# sabotter.net
KiCad netlist of a schematic drawn in EAGLE
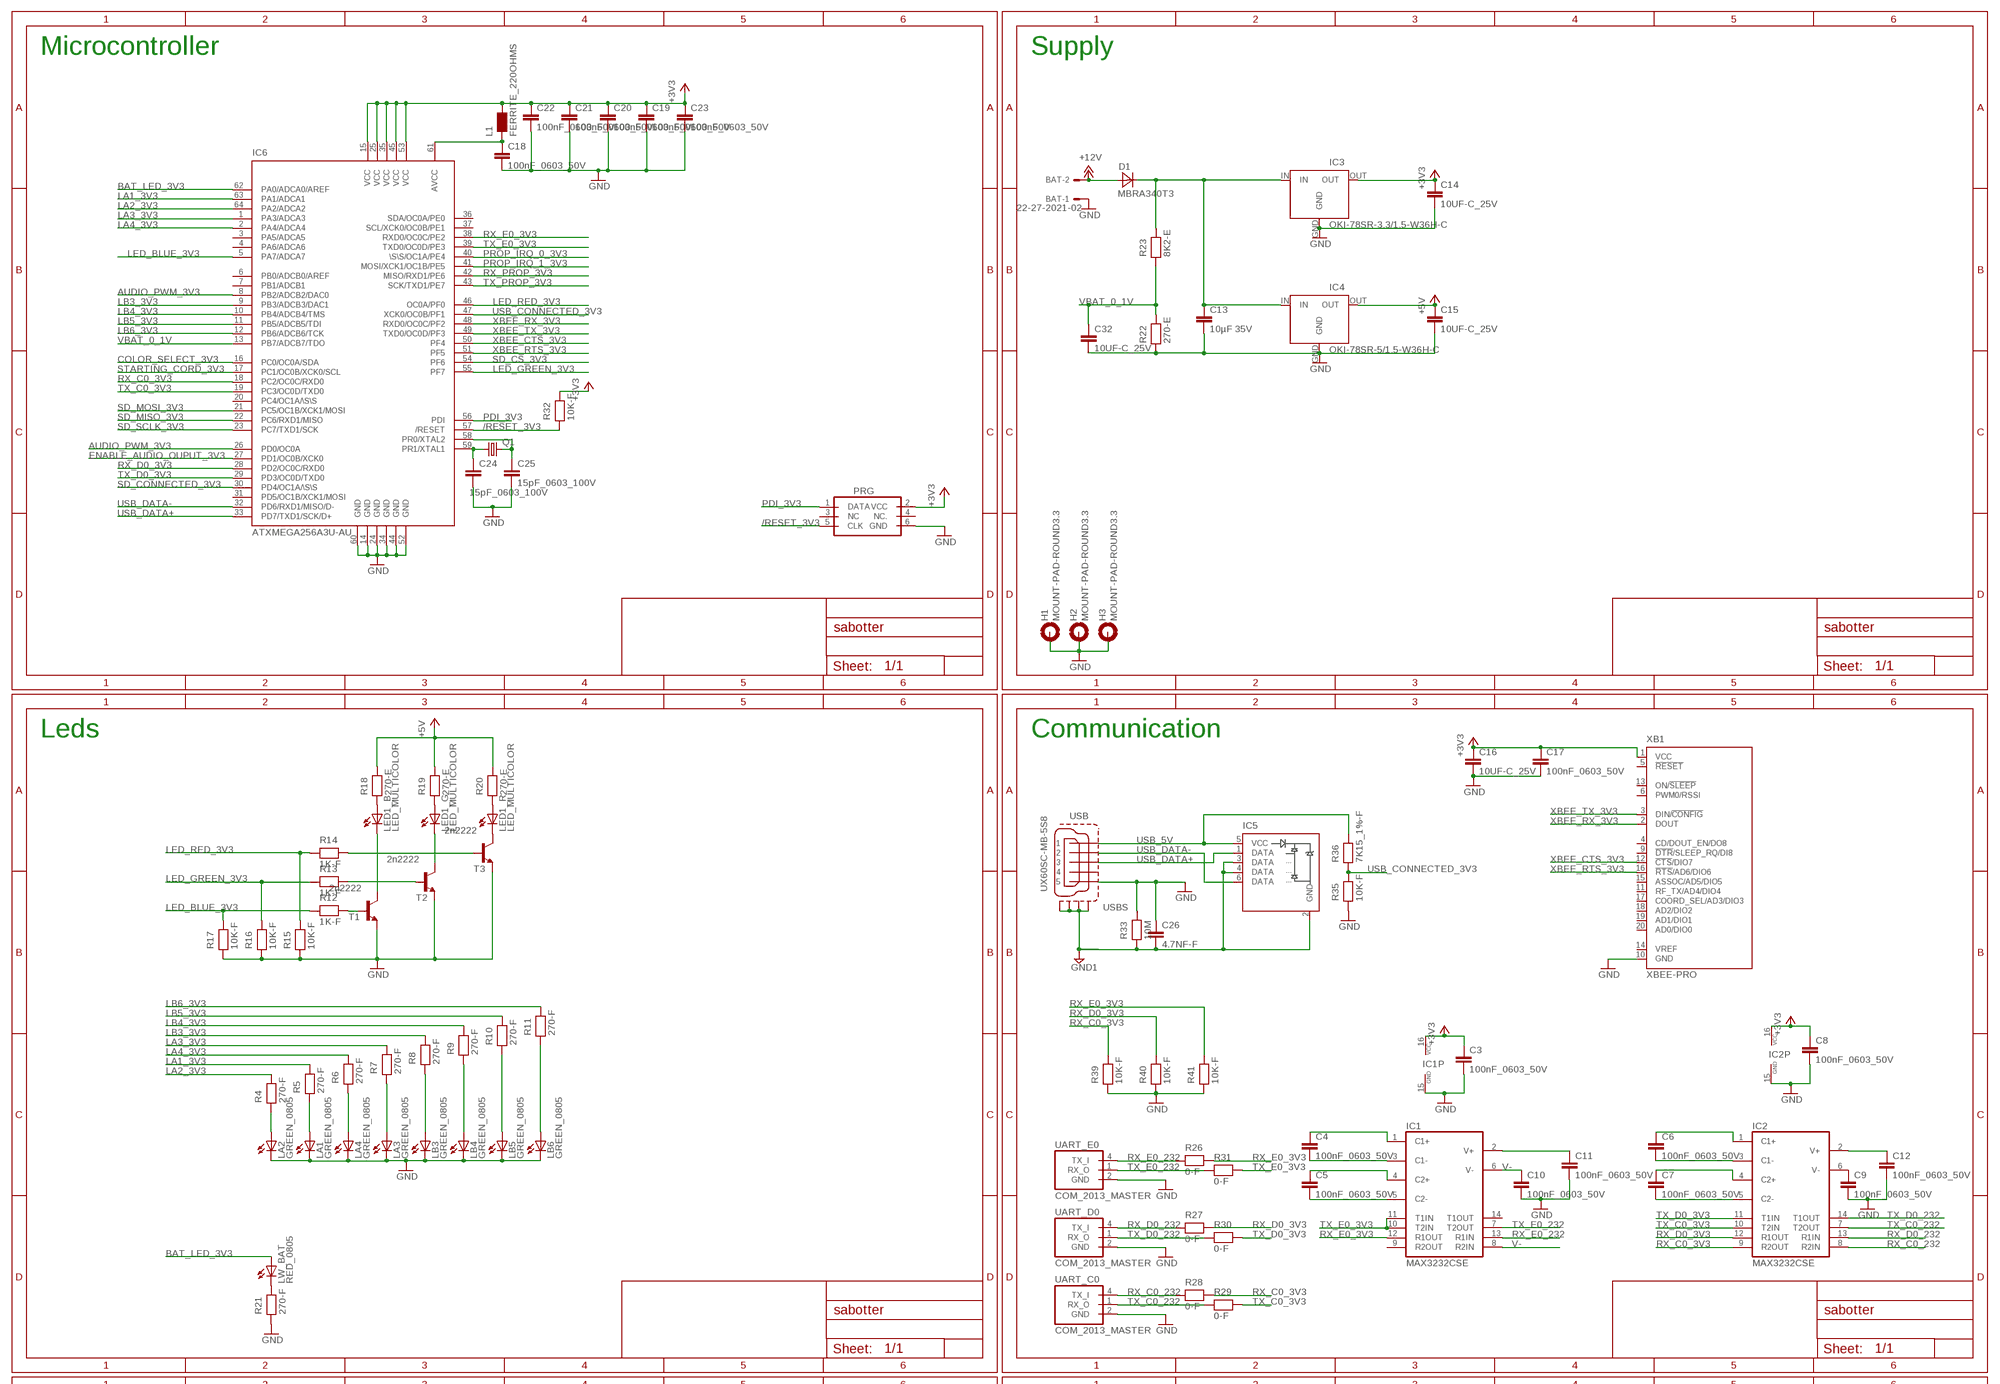
[diagram p0: schematic, sheet 1, part 1 of 2]
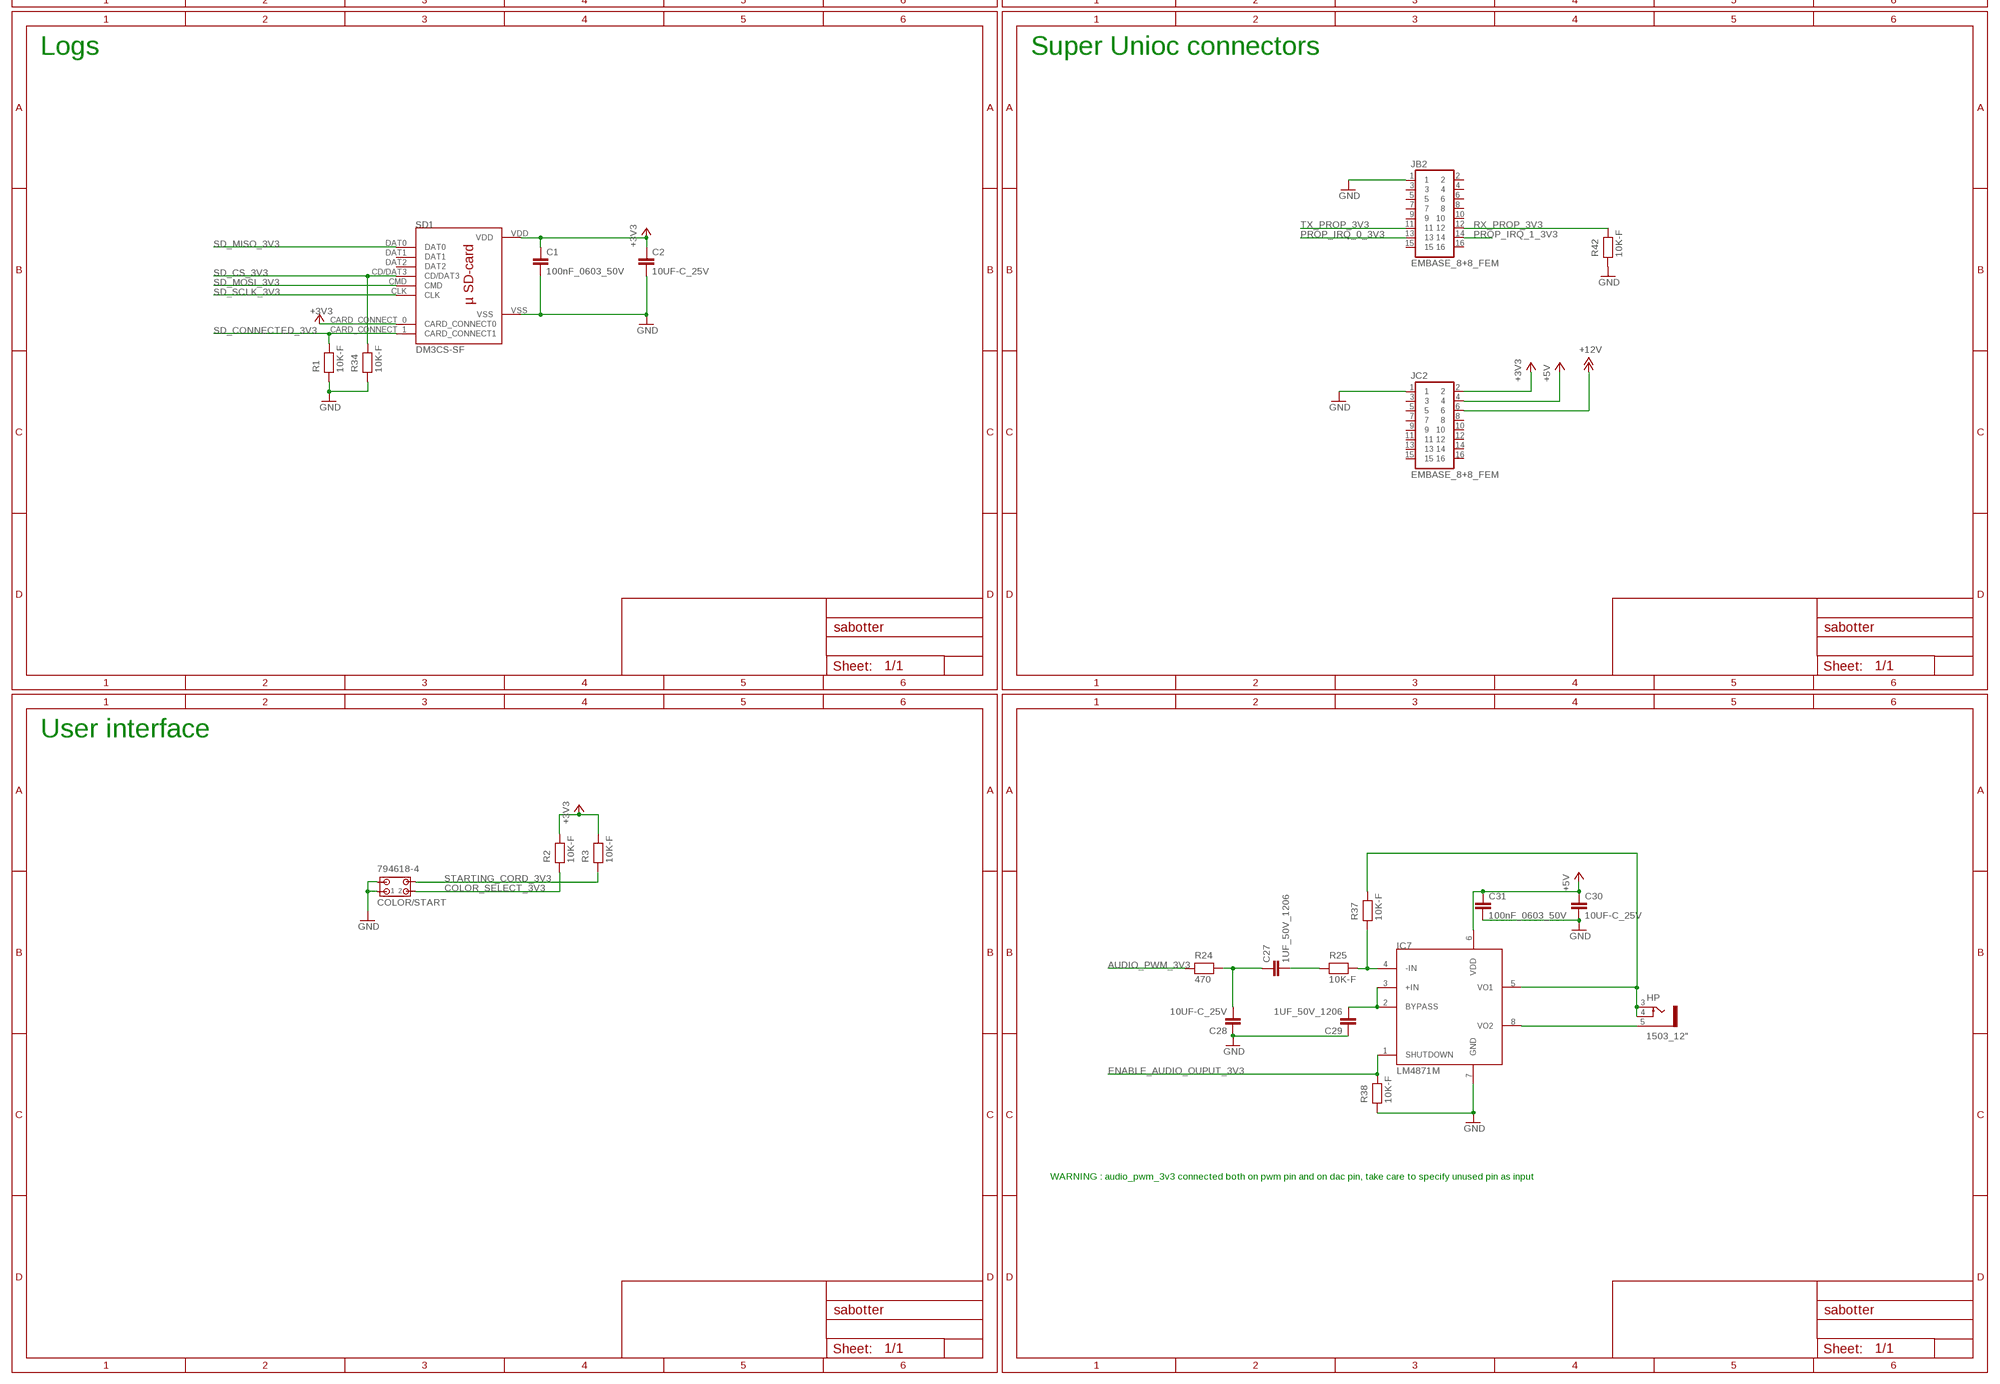
[diagram p1: schematic, sheet 1, part 2 of 2]

(export (version "E")
  (design (tool "Eeschema 10.0.6"))
  (components
    (comp (ref "BAT")
      (value "22-27-2021-02")
      (footprint "eagle-import:6410-02")
      (libsource (lib "eagle-import") (part "22-?-0227-2021"))
    )
    (comp (ref "C1")
      (value "100nF_0603_50V")
      (footprint "eagle-import:C0603")
      (libsource (lib "eagle-import") (part "100NF-F"))
    )
    (comp (ref "C2")
      (value "10UF-C_25V")
      (footprint "eagle-import:C1210")
      (libsource (lib "eagle-import") (part "10UF-C_25V"))
    )
    (comp (ref "C3")
      (value "100nF_0603_50V")
      (footprint "eagle-import:C0603")
      (libsource (lib "eagle-import") (part "100NF-F"))
    )
    (comp (ref "C4")
      (value "100nF_0603_50V")
      (footprint "eagle-import:C0603")
      (libsource (lib "eagle-import") (part "100NF-F"))
    )
    (comp (ref "C5")
      (value "100nF_0603_50V")
      (footprint "eagle-import:C0603")
      (libsource (lib "eagle-import") (part "100NF-F"))
    )
    (comp (ref "C6")
      (value "100nF_0603_50V")
      (footprint "eagle-import:C0603")
      (libsource (lib "eagle-import") (part "100NF-F"))
    )
    (comp (ref "C7")
      (value "100nF_0603_50V")
      (footprint "eagle-import:C0603")
      (libsource (lib "eagle-import") (part "100NF-F"))
    )
    (comp (ref "C8")
      (value "100nF_0603_50V")
      (footprint "eagle-import:C0603")
      (libsource (lib "eagle-import") (part "100NF-F"))
    )
    (comp (ref "C9")
      (value "100nF_0603_50V")
      (footprint "eagle-import:C0603")
      (libsource (lib "eagle-import") (part "100NF-F"))
    )
    (comp (ref "C10")
      (value "100nF_0603_50V")
      (footprint "eagle-import:C0603")
      (libsource (lib "eagle-import") (part "100NF-F"))
    )
    (comp (ref "C11")
      (value "100nF_0603_50V")
      (footprint "eagle-import:C0603")
      (libsource (lib "eagle-import") (part "100NF-F"))
    )
    (comp (ref "C12")
      (value "100nF_0603_50V")
      (footprint "eagle-import:C0603")
      (libsource (lib "eagle-import") (part "100NF-F"))
    )
    (comp (ref "C13")
      (value "10µF 35V")
      (footprint "eagle-import:C1210")
      (libsource (lib "eagle-import") (part "10UF-C_35V"))
    )
    (comp (ref "C14")
      (value "10UF-C_25V")
      (footprint "eagle-import:C1210")
      (libsource (lib "eagle-import") (part "10UF-C_25V"))
    )
    (comp (ref "C15")
      (value "10UF-C_25V")
      (footprint "eagle-import:C1210")
      (libsource (lib "eagle-import") (part "10UF-C_25V"))
    )
    (comp (ref "C16")
      (value "10UF-C_25V")
      (footprint "eagle-import:C1210")
      (libsource (lib "eagle-import") (part "10UF-C_25V"))
    )
    (comp (ref "C17")
      (value "100nF_0603_50V")
      (footprint "eagle-import:C0603")
      (libsource (lib "eagle-import") (part "100NF-F"))
    )
    (comp (ref "C18")
      (value "100nF_0603_50V")
      (footprint "eagle-import:C0603")
      (libsource (lib "eagle-import") (part "100NF-F"))
    )
    (comp (ref "C19")
      (value "100nF_0603_50V")
      (footprint "eagle-import:C0603")
      (libsource (lib "eagle-import") (part "100NF-F"))
    )
    (comp (ref "C20")
      (value "100nF_0603_50V")
      (footprint "eagle-import:C0603")
      (libsource (lib "eagle-import") (part "100NF-F"))
    )
    (comp (ref "C21")
      (value "100nF_0603_50V")
      (footprint "eagle-import:C0603")
      (libsource (lib "eagle-import") (part "100NF-F"))
    )
    (comp (ref "C22")
      (value "100nF_0603_50V")
      (footprint "eagle-import:C0603")
      (libsource (lib "eagle-import") (part "100NF-F"))
    )
    (comp (ref "C23")
      (value "100nF_0603_50V")
      (footprint "eagle-import:C0603")
      (libsource (lib "eagle-import") (part "100NF-F"))
    )
    (comp (ref "C24")
      (value "15pF_0603_100V")
      (footprint "eagle-import:C0603")
      (libsource (lib "eagle-import") (part "15PF-F"))
    )
    (comp (ref "C25")
      (value "15pF_0603_100V")
      (footprint "eagle-import:C0603")
      (libsource (lib "eagle-import") (part "15PF-F"))
    )
    (comp (ref "C26")
      (value "4.7NF-F")
      (footprint "eagle-import:C0603")
      (libsource (lib "eagle-import") (part "4.7NF-F"))
    )
    (comp (ref "C27")
      (value "1UF_50V_1206")
      (footprint "eagle-import:C1206")
      (libsource (lib "eagle-import") (part "1UFD_25V"))
    )
    (comp (ref "C28")
      (value "10UF-C_25V")
      (footprint "eagle-import:C1210")
      (libsource (lib "eagle-import") (part "10UF-C_25V"))
    )
    (comp (ref "C29")
      (value "1UF_50V_1206")
      (footprint "eagle-import:C1206")
      (libsource (lib "eagle-import") (part "1UFD_25V"))
    )
    (comp (ref "C30")
      (value "10UF-C_25V")
      (footprint "eagle-import:C1210")
      (libsource (lib "eagle-import") (part "10UF-C_25V"))
    )
    (comp (ref "C31")
      (value "100nF_0603_50V")
      (footprint "eagle-import:C0603")
      (libsource (lib "eagle-import") (part "100NF-F"))
    )
    (comp (ref "C32")
      (value "10UF-C_25V")
      (footprint "eagle-import:C1210")
      (libsource (lib "eagle-import") (part "10UF-C_25V"))
    )
    (comp (ref "COLOR/START")
      (value "794618-4")
      (footprint "eagle-import:794618-4")
      (libsource (lib "eagle-import") (part "794618-4"))
    )
    (comp (ref "D1")
      (value "MBRA340T3")
      (footprint "eagle-import:SMA")
      (libsource (lib "eagle-import") (part "MBRA340T3"))
    )
    (comp (ref "H1")
      (value "MOUNT-PAD-ROUND3.3")
      (footprint "eagle-import:3,3-PAD")
      (libsource (lib "eagle-import") (part "MOUNT-PAD-ROUND3.3"))
    )
    (comp (ref "H2")
      (value "MOUNT-PAD-ROUND3.3")
      (footprint "eagle-import:3,3-PAD")
      (libsource (lib "eagle-import") (part "MOUNT-PAD-ROUND3.3"))
    )
    (comp (ref "H3")
      (value "MOUNT-PAD-ROUND3.3")
      (footprint "eagle-import:3,3-PAD")
      (libsource (lib "eagle-import") (part "MOUNT-PAD-ROUND3.3"))
    )
    (comp (ref "HP")
      (value "1503_12\"")
      (footprint "eagle-import:1503_12")
      (fields (field (name "MPN") "1503 12"))
      (libsource (lib "eagle-import") (part "1503_12{dblquote}"))
    )
    (comp (ref "IC1")
      (value "MAX3232CSE")
      (footprint "eagle-import:SO16")
      (libsource (lib "eagle-import") (part "MAX3232SEC"))
    )
    (comp (ref "IC2")
      (value "MAX3232CSE")
      (footprint "eagle-import:SO16")
      (libsource (lib "eagle-import") (part "MAX3232SEC"))
    )
    (comp (ref "IC3")
      (value "OKI-78SR-3.3/1.5-W36H-C")
      (footprint "eagle-import:OKI78SR-HORIZONTAL")
      (libsource (lib "eagle-import") (part "OKI-78SR-3.3/1.5-W36H-C"))
    )
    (comp (ref "IC4")
      (value "OKI-78SR-5/1.5-W36H-C")
      (footprint "eagle-import:OKI78SR-HORIZONTAL")
      (libsource (lib "eagle-import") (part "OKI-78SR-5/1.5-W36H-C"))
    )
    (comp (ref "IC5")
      (value "LXES2SBAA4-016")
      (footprint "eagle-import:LXES2BAA4")
      (libsource (lib "eagle-import") (part "LXES2SBAA4-016"))
    )
    (comp (ref "IC6")
      (value "ATXMEGA256A3U-AU")
      (footprint "eagle-import:TQFP64")
      (libsource (lib "eagle-import") (part "ATXMEGA256A3U-AU"))
    )
    (comp (ref "IC7")
      (value "LM4871M")
      (footprint "eagle-import:SO8")
      (libsource (lib "eagle-import") (part "LM4871M"))
    )
    (comp (ref "JB2")
      (value "EMBASE_8+8_FEM")
      (footprint "eagle-import:EMBASE_8+8_FEM")
      (libsource (lib "eagle-import") (part "EMBASE_8+8_FEM"))
    )
    (comp (ref "JC2")
      (value "EMBASE_8+8_FEM")
      (footprint "eagle-import:EMBASE_8+8_FEM")
      (libsource (lib "eagle-import") (part "EMBASE_8+8_FEM"))
    )
    (comp (ref "L1")
      (value "FERRITE_220OHMS")
      (footprint "eagle-import:R0603")
      (libsource (lib "eagle-import") (part "FERRITE_220OHMS"))
    )
    (comp (ref "LA1")
      (value "GREEN_0805")
      (footprint "eagle-import:CHIP-LED0805")
      (libsource (lib "eagle-import") (part "LED_G"))
    )
    (comp (ref "LA2")
      (value "GREEN_0805")
      (footprint "eagle-import:CHIP-LED0805")
      (libsource (lib "eagle-import") (part "LED_G"))
    )
    (comp (ref "LA3")
      (value "GREEN_0805")
      (footprint "eagle-import:CHIP-LED0805")
      (libsource (lib "eagle-import") (part "LED_G"))
    )
    (comp (ref "LA4")
      (value "GREEN_0805")
      (footprint "eagle-import:CHIP-LED0805")
      (libsource (lib "eagle-import") (part "LED_G"))
    )
    (comp (ref "LB3")
      (value "GREEN_0805")
      (footprint "eagle-import:CHIP-LED0805")
      (libsource (lib "eagle-import") (part "LED_G"))
    )
    (comp (ref "LB4")
      (value "GREEN_0805")
      (footprint "eagle-import:CHIP-LED0805")
      (libsource (lib "eagle-import") (part "LED_G"))
    )
    (comp (ref "LB5")
      (value "GREEN_0805")
      (footprint "eagle-import:CHIP-LED0805")
      (libsource (lib "eagle-import") (part "LED_G"))
    )
    (comp (ref "LB6")
      (value "GREEN_0805")
      (footprint "eagle-import:CHIP-LED0805")
      (libsource (lib "eagle-import") (part "LED_G"))
    )
    (comp (ref "LED1")
      (value "LED_MULTICOLOR")
      (footprint "eagle-import:PLCC6")
      (fields (field (name "MANUFACTURER") "AVAGO TECHNOLOGIES"))
      (libsource (lib "eagle-import") (part "LED_MULTICOLOR"))
    )
    (comp (ref "LW_BAT")
      (value "RED_0805")
      (footprint "eagle-import:CHIP-LED0805")
      (libsource (lib "eagle-import") (part "LED_R"))
    )
    (comp (ref "PRG")
      (value "PDI_ATMELL")
      (footprint "eagle-import:ML6L")
      (libsource (lib "eagle-import") (part "PDI_ATMELL"))
    )
    (comp (ref "Q1")
      (value "CRYSTAL_16MHZ_HC49UP")
      (footprint "eagle-import:HC49UP")
      (libsource (lib "eagle-import") (part "CRYSTAL_16MHZ_HC49UP"))
    )
    (comp (ref "R1")
      (value "10K-F")
      (footprint "eagle-import:R0603")
      (libsource (lib "eagle-import") (part "10K-F"))
    )
    (comp (ref "R2")
      (value "10K-F")
      (footprint "eagle-import:R0603")
      (libsource (lib "eagle-import") (part "10K-F"))
    )
    (comp (ref "R3")
      (value "10K-F")
      (footprint "eagle-import:R0603")
      (libsource (lib "eagle-import") (part "10K-F"))
    )
    (comp (ref "R4")
      (value "270-F")
      (footprint "eagle-import:R0603")
      (libsource (lib "eagle-import") (part "270-F"))
    )
    (comp (ref "R5")
      (value "270-F")
      (footprint "eagle-import:R0603")
      (libsource (lib "eagle-import") (part "270-F"))
    )
    (comp (ref "R6")
      (value "270-F")
      (footprint "eagle-import:R0603")
      (libsource (lib "eagle-import") (part "270-F"))
    )
    (comp (ref "R7")
      (value "270-F")
      (footprint "eagle-import:R0603")
      (libsource (lib "eagle-import") (part "270-F"))
    )
    (comp (ref "R8")
      (value "270-F")
      (footprint "eagle-import:R0603")
      (libsource (lib "eagle-import") (part "270-F"))
    )
    (comp (ref "R9")
      (value "270-F")
      (footprint "eagle-import:R0603")
      (libsource (lib "eagle-import") (part "270-F"))
    )
    (comp (ref "R10")
      (value "270-F")
      (footprint "eagle-import:R0603")
      (libsource (lib "eagle-import") (part "270-F"))
    )
    (comp (ref "R11")
      (value "270-F")
      (footprint "eagle-import:R0603")
      (libsource (lib "eagle-import") (part "270-F"))
    )
    (comp (ref "R12")
      (value "1K-F")
      (footprint "eagle-import:R0603")
      (libsource (lib "eagle-import") (part "1K-F"))
    )
    (comp (ref "R13")
      (value "1K-F")
      (footprint "eagle-import:R0603")
      (libsource (lib "eagle-import") (part "1K-F"))
    )
    (comp (ref "R14")
      (value "1K-F")
      (footprint "eagle-import:R0603")
      (libsource (lib "eagle-import") (part "1K-F"))
    )
    (comp (ref "R15")
      (value "10K-F")
      (footprint "eagle-import:R0603")
      (libsource (lib "eagle-import") (part "10K-F"))
    )
    (comp (ref "R16")
      (value "10K-F")
      (footprint "eagle-import:R0603")
      (libsource (lib "eagle-import") (part "10K-F"))
    )
    (comp (ref "R17")
      (value "10K-F")
      (footprint "eagle-import:R0603")
      (libsource (lib "eagle-import") (part "10K-F"))
    )
    (comp (ref "R18")
      (value "270-E")
      (footprint "eagle-import:R0805")
      (libsource (lib "eagle-import") (part "270-E"))
    )
    (comp (ref "R19")
      (value "270-E")
      (footprint "eagle-import:R0805")
      (libsource (lib "eagle-import") (part "270-E"))
    )
    (comp (ref "R20")
      (value "270-E")
      (footprint "eagle-import:R0805")
      (libsource (lib "eagle-import") (part "270-E"))
    )
    (comp (ref "R21")
      (value "270-F")
      (footprint "eagle-import:R0603")
      (libsource (lib "eagle-import") (part "270-F"))
    )
    (comp (ref "R22")
      (value "270-E")
      (footprint "eagle-import:R0805")
      (libsource (lib "eagle-import") (part "270-E"))
    )
    (comp (ref "R23")
      (value "8K2-E")
      (footprint "eagle-import:R0805")
      (libsource (lib "eagle-import") (part "8K2-E"))
    )
    (comp (ref "R24")
      (value "470")
      (footprint "eagle-import:R0603")
      (libsource (lib "eagle-import") (part "470-F"))
    )
    (comp (ref "R25")
      (value "10K-F")
      (footprint "eagle-import:R0603")
      (libsource (lib "eagle-import") (part "10K-F"))
    )
    (comp (ref "R26")
      (value "0-F")
      (footprint "eagle-import:R0603")
      (libsource (lib "eagle-import") (part "0-F"))
    )
    (comp (ref "R27")
      (value "0-F")
      (footprint "eagle-import:R0603")
      (libsource (lib "eagle-import") (part "0-F"))
    )
    (comp (ref "R28")
      (value "0-F")
      (footprint "eagle-import:R0603")
      (libsource (lib "eagle-import") (part "0-F"))
    )
    (comp (ref "R29")
      (value "0-F")
      (footprint "eagle-import:R0603")
      (libsource (lib "eagle-import") (part "0-F"))
    )
    (comp (ref "R30")
      (value "0-F")
      (footprint "eagle-import:R0603")
      (libsource (lib "eagle-import") (part "0-F"))
    )
    (comp (ref "R31")
      (value "0-F")
      (footprint "eagle-import:R0603")
      (libsource (lib "eagle-import") (part "0-F"))
    )
    (comp (ref "R32")
      (value "10K-F")
      (footprint "eagle-import:R0603")
      (libsource (lib "eagle-import") (part "10K-F"))
    )
    (comp (ref "R33")
      (value "10M")
      (footprint "eagle-import:R0603")
      (libsource (lib "eagle-import") (part "1M-F"))
    )
    (comp (ref "R34")
      (value "10K-F")
      (footprint "eagle-import:R0603")
      (libsource (lib "eagle-import") (part "10K-F"))
    )
    (comp (ref "R35")
      (value "10K-F")
      (footprint "eagle-import:R0603")
      (libsource (lib "eagle-import") (part "10K-F"))
    )
    (comp (ref "R36")
      (value "7K15_1%-F")
      (footprint "eagle-import:R0603")
      (libsource (lib "eagle-import") (part "7K15_1%-F"))
    )
    (comp (ref "R37")
      (value "10K-F")
      (footprint "eagle-import:R0603")
      (libsource (lib "eagle-import") (part "10K-F"))
    )
    (comp (ref "R38")
      (value "10K-F")
      (footprint "eagle-import:R0603")
      (libsource (lib "eagle-import") (part "10K-F"))
    )
    (comp (ref "R39")
      (value "10K-F")
      (footprint "eagle-import:R0603")
      (libsource (lib "eagle-import") (part "10K-F"))
    )
    (comp (ref "R40")
      (value "10K-F")
      (footprint "eagle-import:R0603")
      (libsource (lib "eagle-import") (part "10K-F"))
    )
    (comp (ref "R41")
      (value "10K-F")
      (footprint "eagle-import:R0603")
      (libsource (lib "eagle-import") (part "10K-F"))
    )
    (comp (ref "R42")
      (value "10K-F")
      (footprint "eagle-import:R0603")
      (libsource (lib "eagle-import") (part "10K-F"))
    )
    (comp (ref "SD1")
      (value "DM3CS-SF")
      (footprint "eagle-import:DM3CS-SF")
      (libsource (lib "eagle-import") (part "DM3CS-SF"))
    )
    (comp (ref "T1")
      (value "2n2222")
      (footprint "eagle-import:SOT23-BEC")
      (libsource (lib "eagle-import") (part "-NPN-SOT23-BECMMBT2222ALT1"))
    )
    (comp (ref "T2")
      (value "2n2222")
      (footprint "eagle-import:SOT23-BEC")
      (libsource (lib "eagle-import") (part "-NPN-SOT23-BECMMBT2222ALT1"))
    )
    (comp (ref "T3")
      (value "2n2222")
      (footprint "eagle-import:SOT23-BEC")
      (libsource (lib "eagle-import") (part "-NPN-SOT23-BECMMBT2222ALT1"))
    )
    (comp (ref "UART_C0")
      (value "COM_2013_MASTER")
      (footprint "eagle-import:MICROMATCH-4_SMD")
      (libsource (lib "eagle-import") (part "COM_2013_MASTER"))
    )
    (comp (ref "UART_D0")
      (value "COM_2013_MASTER")
      (footprint "eagle-import:MICROMATCH-4_SMD")
      (libsource (lib "eagle-import") (part "COM_2013_MASTER"))
    )
    (comp (ref "UART_E0")
      (value "COM_2013_MASTER")
      (footprint "eagle-import:MICROMATCH-4_SMD")
      (libsource (lib "eagle-import") (part "COM_2013_MASTER"))
    )
    (comp (ref "USB")
      (value "UX60SC-MB-5S8")
      (footprint "eagle-import:UX60-MB-5S8")
      (libsource (lib "eagle-import") (part "MINI-USB-SHIELD-UX60-MB-5S8"))
    )
    (comp (ref "XB1")
      (value "XBEE-PRO")
      (footprint "eagle-import:XBEE-PRO")
      (fields (field (name "MPN") "XBP24-AWI-001"))
      (libsource (lib "eagle-import") (part "XBEE-PRO"))
    )
  )
  (nets
    (net (code "1") (name "+3V3") (class "Default")
      (node (ref "C1") (pin "1") (pinfunction "1_1") (pintype "passive"))
      (node (ref "C14") (pin "1") (pinfunction "1_1") (pintype "passive"))
      (node (ref "C16") (pin "1") (pinfunction "1_1") (pintype "passive"))
      (node (ref "C17") (pin "1") (pinfunction "1_1") (pintype "passive"))
      (node (ref "C19") (pin "1") (pinfunction "1_1") (pintype "passive"))
      (node (ref "C2") (pin "1") (pinfunction "1_1") (pintype "passive"))
      (node (ref "C20") (pin "1") (pinfunction "1_1") (pintype "passive"))
      (node (ref "C21") (pin "1") (pinfunction "1_1") (pintype "passive"))
      (node (ref "C22") (pin "1") (pinfunction "1_1") (pintype "passive"))
      (node (ref "C23") (pin "1") (pinfunction "1_1") (pintype "passive"))
      (node (ref "C3") (pin "1") (pinfunction "1_1") (pintype "passive"))
      (node (ref "C8") (pin "1") (pinfunction "1_1") (pintype "passive"))
      (node (ref "IC1") (pin "16") (pinfunction "VCC_16") (pintype "power_in"))
      (node (ref "IC2") (pin "16") (pinfunction "VCC_16") (pintype "power_in"))
      (node (ref "IC3") (pin "OUT") (pinfunction "OUT_OUT") (pintype "bidirectional"))
      (node (ref "IC6") (pin "15") (pinfunction "VCC_15") (pintype "bidirectional"))
      (node (ref "IC6") (pin "25") (pinfunction "VCC_25") (pintype "bidirectional"))
      (node (ref "IC6") (pin "35") (pinfunction "VCC_35") (pintype "bidirectional"))
      (node (ref "IC6") (pin "45") (pinfunction "VCC_45") (pintype "bidirectional"))
      (node (ref "IC6") (pin "53") (pinfunction "VCC_53") (pintype "bidirectional"))
      (node (ref "JC2") (pin "2") (pinfunction "2_2") (pintype "passive"))
      (node (ref "L1") (pin "2") (pinfunction "2_2") (pintype "passive"))
      (node (ref "PRG") (pin "2") (pinfunction "VCC_2") (pintype "passive"))
      (node (ref "R2") (pin "2") (pinfunction "2_2") (pintype "bidirectional"))
      (node (ref "R3") (pin "2") (pinfunction "2_2") (pintype "bidirectional"))
      (node (ref "R32") (pin "2") (pinfunction "2_2") (pintype "bidirectional"))
      (node (ref "SD1") (pin "CARD_CONNECT_0") (pinfunction "CARD_CONNECT0_CARD_CONNECT_0") (pintype "bidirectional"))
      (node (ref "SD1") (pin "VDD") (pinfunction "VDD_VDD") (pintype "bidirectional"))
      (node (ref "XB1") (pin "1") (pinfunction "VCC_1") (pintype "power_in"))
    )
    (net (code "2") (name "+5V") (class "Default")
      (node (ref "C15") (pin "1") (pinfunction "1_1") (pintype "passive"))
      (node (ref "C30") (pin "1") (pinfunction "1_1") (pintype "passive"))
      (node (ref "C31") (pin "1") (pinfunction "1_1") (pintype "passive"))
      (node (ref "IC4") (pin "OUT") (pinfunction "OUT_OUT") (pintype "bidirectional"))
      (node (ref "IC7") (pin "6") (pinfunction "VDD_6") (pintype "bidirectional"))
      (node (ref "JC2") (pin "4") (pinfunction "4_4") (pintype "passive"))
      (node (ref "R18") (pin "2") (pinfunction "2_2") (pintype "bidirectional"))
      (node (ref "R19") (pin "2") (pinfunction "2_2") (pintype "bidirectional"))
      (node (ref "R20") (pin "2") (pinfunction "2_2") (pintype "bidirectional"))
    )
    (net (code "3") (name "+12V") (class "Default")
      (node (ref "BAT") (pin "2") (pinfunction "S_2") (pintype "passive"))
      (node (ref "D1") (pin "A") (pinfunction "A_A") (pintype "passive"))
      (node (ref "JC2") (pin "6") (pinfunction "6_6") (pintype "passive"))
    )
    (net (code "4") (name "/AUDIO_PWM_3V3") (class "Default")
      (node (ref "IC6") (pin "26") (pinfunction "PD0/OC0A_26") (pintype "bidirectional"))
      (node (ref "IC6") (pin "8") (pinfunction "PB2/ADCB2/DAC0_8") (pintype "bidirectional"))
      (node (ref "R24") (pin "1") (pinfunction "1_1") (pintype "bidirectional"))
    )
    (net (code "5") (name "/BAT_LED_3V3") (class "Default")
      (node (ref "IC6") (pin "62") (pinfunction "PA0/ADCA0/AREF_62") (pintype "bidirectional"))
      (node (ref "LW_BAT") (pin "A") (pinfunction "A_A") (pintype "passive"))
    )
    (net (code "6") (name "/COLOR_SELECT_3V3") (class "Default")
      (node (ref "COLOR/START") (pin "2") (pinfunction "2_2") (pintype "passive"))
      (node (ref "IC6") (pin "16") (pinfunction "PC0/OC0A/SDA_16") (pintype "bidirectional"))
      (node (ref "R2") (pin "1") (pinfunction "1_1") (pintype "bidirectional"))
    )
    (net (code "7") (name "/ENABLE_AUDIO_OUPUT_3V3") (class "Default")
      (node (ref "IC6") (pin "27") (pinfunction "PD1/OC0B/XCK0_27") (pintype "bidirectional"))
      (node (ref "IC7") (pin "1") (pinfunction "SHUTDOWN_1") (pintype "bidirectional"))
      (node (ref "R38") (pin "2") (pinfunction "2_2") (pintype "bidirectional"))
    )
    (net (code "8") (name "/LA1_3V3") (class "Default")
      (node (ref "IC6") (pin "63") (pinfunction "PA1/ADCA1_63") (pintype "bidirectional"))
      (node (ref "R5") (pin "2") (pinfunction "2_2") (pintype "bidirectional"))
    )
    (net (code "9") (name "/LA2_3V3") (class "Default")
      (node (ref "IC6") (pin "64") (pinfunction "PA2/ADCA2_64") (pintype "bidirectional"))
      (node (ref "R4") (pin "2") (pinfunction "2_2") (pintype "bidirectional"))
    )
    (net (code "10") (name "/LA3_3V3") (class "Default")
      (node (ref "IC6") (pin "1") (pinfunction "PA3/ADCA3_1") (pintype "bidirectional"))
      (node (ref "R7") (pin "2") (pinfunction "2_2") (pintype "bidirectional"))
    )
    (net (code "11") (name "/LA4_3V3") (class "Default")
      (node (ref "IC6") (pin "2") (pinfunction "PA4/ADCA4_2") (pintype "bidirectional"))
      (node (ref "R6") (pin "2") (pinfunction "2_2") (pintype "bidirectional"))
    )
    (net (code "12") (name "/LB3_3V3") (class "Default")
      (node (ref "IC6") (pin "9") (pinfunction "PB3/ADCB3/DAC1_9") (pintype "bidirectional"))
      (node (ref "R8") (pin "2") (pinfunction "2_2") (pintype "bidirectional"))
    )
    (net (code "13") (name "/LB4_3V3") (class "Default")
      (node (ref "IC6") (pin "10") (pinfunction "PB4/ADCB4/TMS_10") (pintype "bidirectional"))
      (node (ref "R9") (pin "2") (pinfunction "2_2") (pintype "bidirectional"))
    )
    (net (code "14") (name "/LB5_3V3") (class "Default")
      (node (ref "IC6") (pin "11") (pinfunction "PB5/ADCB5/TDI_11") (pintype "bidirectional"))
      (node (ref "R10") (pin "2") (pinfunction "2_2") (pintype "bidirectional"))
    )
    (net (code "15") (name "/LB6_3V3") (class "Default")
      (node (ref "IC6") (pin "12") (pinfunction "PB6/ADCB6/TCK_12") (pintype "bidirectional"))
      (node (ref "R11") (pin "2") (pinfunction "2_2") (pintype "bidirectional"))
    )
    (net (code "16") (name "/LED_BLUE_3V3") (class "Default")
      (node (ref "IC6") (pin "5") (pinfunction "PA7/ADCA7_5") (pintype "bidirectional"))
      (node (ref "R12") (pin "1") (pinfunction "1_1") (pintype "bidirectional"))
      (node (ref "R17") (pin "2") (pinfunction "2_2") (pintype "bidirectional"))
    )
    (net (code "17") (name "/LED_GREEN_3V3") (class "Default")
      (node (ref "IC6") (pin "55") (pinfunction "PF7_55") (pintype "bidirectional"))
      (node (ref "R13") (pin "1") (pinfunction "1_1") (pintype "bidirectional"))
      (node (ref "R16") (pin "2") (pinfunction "2_2") (pintype "bidirectional"))
    )
    (net (code "18") (name "/LED_RED_3V3") (class "Default")
      (node (ref "IC6") (pin "46") (pinfunction "OC0A/PF0_46") (pintype "bidirectional"))
      (node (ref "R14") (pin "1") (pinfunction "1_1") (pintype "bidirectional"))
      (node (ref "R15") (pin "2") (pinfunction "2_2") (pintype "bidirectional"))
    )
    (net (code "19") (name "/PDI_3V3") (class "Default")
      (node (ref "IC6") (pin "56") (pinfunction "PDI_56") (pintype "bidirectional"))
      (node (ref "PRG") (pin "1") (pinfunction "DATA_1") (pintype "passive"))
    )
    (net (code "20") (name "/PROP_IRQ_0_3V3") (class "Default")
      (node (ref "IC6") (pin "40") (pinfunction "\\S\\S/OC1A/PE4_40") (pintype "bidirectional"))
      (node (ref "JB2") (pin "13") (pinfunction "13_13") (pintype "passive"))
    )
    (net (code "21") (name "/PROP_IRQ_1_3V3") (class "Default")
      (node (ref "IC6") (pin "41") (pinfunction "MOSI/XCK1/OC1B/PE5_41") (pintype "bidirectional"))
      (node (ref "JB2") (pin "14") (pinfunction "14_14") (pintype "passive"))
    )
    (net (code "22") (name "/RX_C0_3V3") (class "Default")
      (node (ref "IC2") (pin "9") (pinfunction "R2OUT_9") (pintype "output"))
      (node (ref "IC6") (pin "18") (pinfunction "PC2/OC0C/RXD0_18") (pintype "bidirectional"))
      (node (ref "R28") (pin "2") (pinfunction "2_2") (pintype "bidirectional"))
      (node (ref "R39") (pin "2") (pinfunction "2_2") (pintype "bidirectional"))
    )
    (net (code "23") (name "/RX_C0_232") (class "Default")
      (node (ref "IC2") (pin "8") (pinfunction "R2IN_8") (pintype "input"))
      (node (ref "R28") (pin "1") (pinfunction "1_1") (pintype "bidirectional"))
      (node (ref "UART_C0") (pin "4") (pinfunction "TX_I_4") (pintype "passive"))
    )
    (net (code "24") (name "/RX_D0_3V3") (class "Default")
      (node (ref "IC2") (pin "12") (pinfunction "R1OUT_12") (pintype "output"))
      (node (ref "IC6") (pin "28") (pinfunction "PD2/OC0C/RXD0_28") (pintype "bidirectional"))
      (node (ref "R27") (pin "2") (pinfunction "2_2") (pintype "bidirectional"))
      (node (ref "R40") (pin "2") (pinfunction "2_2") (pintype "bidirectional"))
    )
    (net (code "25") (name "/RX_D0_232") (class "Default")
      (node (ref "IC2") (pin "13") (pinfunction "R1IN_13") (pintype "input"))
      (node (ref "R27") (pin "1") (pinfunction "1_1") (pintype "bidirectional"))
      (node (ref "UART_D0") (pin "4") (pinfunction "TX_I_4") (pintype "passive"))
    )
    (net (code "26") (name "/RX_E0_3V3") (class "Default")
      (node (ref "IC1") (pin "12") (pinfunction "R1OUT_12") (pintype "output"))
      (node (ref "IC6") (pin "38") (pinfunction "RXD0/OC0C/PE2_38") (pintype "bidirectional"))
      (node (ref "R26") (pin "2") (pinfunction "2_2") (pintype "bidirectional"))
      (node (ref "R41") (pin "2") (pinfunction "2_2") (pintype "bidirectional"))
    )
    (net (code "27") (name "/RX_E0_232") (class "Default")
      (node (ref "IC1") (pin "13") (pinfunction "R1IN_13") (pintype "input"))
      (node (ref "R26") (pin "1") (pinfunction "1_1") (pintype "bidirectional"))
      (node (ref "UART_E0") (pin "4") (pinfunction "TX_I_4") (pintype "passive"))
    )
    (net (code "28") (name "/RX_PROP_3V3") (class "Default")
      (node (ref "IC6") (pin "42") (pinfunction "MISO/RXD1/PE6_42") (pintype "bidirectional"))
      (node (ref "JB2") (pin "12") (pinfunction "12_12") (pintype "passive"))
      (node (ref "R42") (pin "2") (pinfunction "2_2") (pintype "bidirectional"))
    )
    (net (code "29") (name "/SD_CONNECTED_3V3") (class "Default")
      (node (ref "IC6") (pin "30") (pinfunction "PD4/OC1A/\\S\\S_30") (pintype "bidirectional"))
      (node (ref "R1") (pin "2") (pinfunction "2_2") (pintype "bidirectional"))
      (node (ref "SD1") (pin "CARD_CONNECT_1") (pinfunction "CARD_CONNECT1_CARD_CONNECT_1") (pintype "bidirectional"))
    )
    (net (code "30") (name "/SD_CS_3V3") (class "Default")
      (node (ref "IC6") (pin "54") (pinfunction "PF6_54") (pintype "bidirectional"))
      (node (ref "R34") (pin "2") (pinfunction "2_2") (pintype "bidirectional"))
      (node (ref "SD1") (pin "CD/DAT3") (pinfunction "CD/DAT3_CD/DAT3") (pintype "bidirectional"))
    )
    (net (code "31") (name "/SD_MISO_3V3") (class "Default")
      (node (ref "IC6") (pin "22") (pinfunction "PC6/RXD1/MISO_22") (pintype "bidirectional"))
      (node (ref "SD1") (pin "DAT0") (pinfunction "DAT0_DAT0") (pintype "bidirectional"))
    )
    (net (code "32") (name "/SD_MOSI_3V3") (class "Default")
      (node (ref "IC6") (pin "21") (pinfunction "PC5/OC1B/XCK1/MOSI_21") (pintype "bidirectional"))
      (node (ref "SD1") (pin "CMD") (pinfunction "CMD_CMD") (pintype "bidirectional"))
    )
    (net (code "33") (name "/SD_SCLK_3V3") (class "Default")
      (node (ref "IC6") (pin "23") (pinfunction "PC7/TXD1/SCK_23") (pintype "bidirectional"))
      (node (ref "SD1") (pin "CLK") (pinfunction "CLK_CLK") (pintype "bidirectional"))
    )
    (net (code "34") (name "/STARTING_CORD_3V3") (class "Default")
      (node (ref "COLOR/START") (pin "4") (pinfunction "4_4") (pintype "passive"))
      (node (ref "IC6") (pin "17") (pinfunction "PC1/OC0B/XCK0/SCL_17") (pintype "bidirectional"))
      (node (ref "R3") (pin "1") (pinfunction "1_1") (pintype "bidirectional"))
    )
    (net (code "35") (name "/TX_C0_3V3") (class "Default")
      (node (ref "IC2") (pin "10") (pinfunction "T2IN_10") (pintype "input"))
      (node (ref "IC6") (pin "19") (pinfunction "PC3/OC0D/TXD0_19") (pintype "bidirectional"))
      (node (ref "R29") (pin "2") (pinfunction "2_2") (pintype "bidirectional"))
    )
    (net (code "36") (name "/TX_C0_232") (class "Default")
      (node (ref "IC2") (pin "7") (pinfunction "T2OUT_7") (pintype "output"))
      (node (ref "R29") (pin "1") (pinfunction "1_1") (pintype "bidirectional"))
      (node (ref "UART_C0") (pin "1") (pinfunction "RX_O_1") (pintype "passive"))
    )
    (net (code "37") (name "/TX_D0_3V3") (class "Default")
      (node (ref "IC2") (pin "11") (pinfunction "T1IN_11") (pintype "input"))
      (node (ref "IC6") (pin "29") (pinfunction "PD3/OC0D/TXD0_29") (pintype "bidirectional"))
      (node (ref "R30") (pin "2") (pinfunction "2_2") (pintype "bidirectional"))
    )
    (net (code "38") (name "/TX_D0_232") (class "Default")
      (node (ref "IC2") (pin "14") (pinfunction "T1OUT_14") (pintype "output"))
      (node (ref "R30") (pin "1") (pinfunction "1_1") (pintype "bidirectional"))
      (node (ref "UART_D0") (pin "1") (pinfunction "RX_O_1") (pintype "passive"))
    )
    (net (code "39") (name "/TX_E0_3V3") (class "Default")
      (node (ref "IC1") (pin "10") (pinfunction "T2IN_10") (pintype "input"))
      (node (ref "IC1") (pin "11") (pinfunction "T1IN_11") (pintype "input"))
      (node (ref "IC6") (pin "39") (pinfunction "TXD0/OC0D/PE3_39") (pintype "bidirectional"))
      (node (ref "R31") (pin "2") (pinfunction "2_2") (pintype "bidirectional"))
    )
    (net (code "40") (name "/TX_E0_232") (class "Default")
      (node (ref "IC1") (pin "7") (pinfunction "T2OUT_7") (pintype "output"))
      (node (ref "R31") (pin "1") (pinfunction "1_1") (pintype "bidirectional"))
      (node (ref "UART_E0") (pin "1") (pinfunction "RX_O_1") (pintype "passive"))
    )
    (net (code "41") (name "/TX_PROP_3V3") (class "Default")
      (node (ref "IC6") (pin "43") (pinfunction "SCK/TXD1/PE7_43") (pintype "bidirectional"))
      (node (ref "JB2") (pin "11") (pinfunction "11_11") (pintype "passive"))
    )
    (net (code "42") (name "/USB_5V") (class "Default")
      (node (ref "IC5") (pin "5") (pinfunction "VCC_5") (pintype "bidirectional"))
      (node (ref "R36") (pin "2") (pinfunction "2_2") (pintype "bidirectional"))
      (node (ref "USB") (pin "1") (pinfunction "1_1") (pintype "input"))
    )
    (net (code "43") (name "/USB_CONNECTED_3V3") (class "Default")
      (node (ref "IC6") (pin "47") (pinfunction "XCK0/OC0B/PF1_47") (pintype "bidirectional"))
      (node (ref "R35") (pin "2") (pinfunction "2_2") (pintype "bidirectional"))
      (node (ref "R36") (pin "1") (pinfunction "1_1") (pintype "bidirectional"))
    )
    (net (code "44") (name "/USB_DATA+") (class "Default")
      (node (ref "IC5") (pin "1") (pinfunction "DATA_1") (pintype "bidirectional"))
      (node (ref "IC6") (pin "33") (pinfunction "PD7/TXD1/SCK/D+_33") (pintype "bidirectional"))
      (node (ref "USB") (pin "3") (pinfunction "3_3") (pintype "input"))
    )
    (net (code "45") (name "/USB_DATA-") (class "Default")
      (node (ref "IC5") (pin "6") (pinfunction "DATA_6") (pintype "bidirectional"))
      (node (ref "IC6") (pin "32") (pinfunction "PD6/RXD1/MISO/D-_32") (pintype "bidirectional"))
      (node (ref "USB") (pin "2") (pinfunction "2_2") (pintype "input"))
    )
    (net (code "46") (name "/V-") (class "Default")
      (node (ref "C10") (pin "1") (pinfunction "1_1") (pintype "passive"))
      (node (ref "IC1") (pin "6") (pinfunction "V-_6") (pintype "bidirectional"))
      (node (ref "IC1") (pin "8") (pinfunction "R2IN_8") (pintype "input"))
    )
    (net (code "47") (name "/VBAT_0_1V") (class "Default")
      (node (ref "C32") (pin "1") (pinfunction "1_1") (pintype "passive"))
      (node (ref "IC6") (pin "13") (pinfunction "PB7/ADCB7/TDO_13") (pintype "bidirectional"))
      (node (ref "R22") (pin "2") (pinfunction "2_2") (pintype "bidirectional"))
      (node (ref "R23") (pin "1") (pinfunction "1_1") (pintype "bidirectional"))
    )
    (net (code "48") (name "/XBEE_CTS_3V3") (class "Default")
      (node (ref "IC6") (pin "50") (pinfunction "PF4_50") (pintype "bidirectional"))
      (node (ref "XB1") (pin "12") (pinfunction "~{CTS}/DIO7_12") (pintype "bidirectional"))
    )
    (net (code "49") (name "/XBEE_RTS_3V3") (class "Default")
      (node (ref "IC6") (pin "51") (pinfunction "PF5_51") (pintype "bidirectional"))
      (node (ref "XB1") (pin "16") (pinfunction "~{RTS}/AD6/DIO6_16") (pintype "bidirectional"))
    )
    (net (code "50") (name "/XBEE_RX_3V3") (class "Default")
      (node (ref "IC6") (pin "48") (pinfunction "RXD0/OC0C/PF2_48") (pintype "bidirectional"))
      (node (ref "XB1") (pin "2") (pinfunction "DOUT_2") (pintype "output"))
    )
    (net (code "51") (name "/XBEE_TX_3V3") (class "Default")
      (node (ref "IC6") (pin "49") (pinfunction "TXD0/OC0D/PF3_49") (pintype "bidirectional"))
      (node (ref "XB1") (pin "3") (pinfunction "DIN/~{CONFIG}_3") (pintype "input"))
    )
    (net (code "52") (name "/{slash}RESET_3V3") (class "Default")
      (node (ref "IC6") (pin "57") (pinfunction "/RESET_57") (pintype "bidirectional"))
      (node (ref "PRG") (pin "5") (pinfunction "CLK_5") (pintype "passive"))
      (node (ref "R32") (pin "1") (pinfunction "1_1") (pintype "bidirectional"))
    )
    (net (code "53") (name "GND") (class "Default")
      (node (ref "BAT") (pin "1") (pinfunction "S_1") (pintype "passive"))
      (node (ref "C1") (pin "2") (pinfunction "2_2") (pintype "passive"))
      (node (ref "C10") (pin "2") (pinfunction "2_2") (pintype "passive"))
      (node (ref "C11") (pin "2") (pinfunction "2_2") (pintype "passive"))
      (node (ref "C12") (pin "2") (pinfunction "2_2") (pintype "passive"))
      (node (ref "C13") (pin "2") (pinfunction "2_2") (pintype "passive"))
      (node (ref "C14") (pin "2") (pinfunction "2_2") (pintype "passive"))
      (node (ref "C15") (pin "2") (pinfunction "2_2") (pintype "passive"))
      (node (ref "C16") (pin "2") (pinfunction "2_2") (pintype "passive"))
      (node (ref "C17") (pin "2") (pinfunction "2_2") (pintype "passive"))
      (node (ref "C18") (pin "2") (pinfunction "2_2") (pintype "passive"))
      (node (ref "C19") (pin "2") (pinfunction "2_2") (pintype "passive"))
      (node (ref "C2") (pin "2") (pinfunction "2_2") (pintype "passive"))
      (node (ref "C20") (pin "2") (pinfunction "2_2") (pintype "passive"))
      (node (ref "C21") (pin "2") (pinfunction "2_2") (pintype "passive"))
      (node (ref "C22") (pin "2") (pinfunction "2_2") (pintype "passive"))
      (node (ref "C23") (pin "2") (pinfunction "2_2") (pintype "passive"))
      (node (ref "C24") (pin "2") (pinfunction "2_2") (pintype "passive"))
      (node (ref "C25") (pin "2") (pinfunction "2_2") (pintype "passive"))
      (node (ref "C26") (pin "1") (pinfunction "1_1") (pintype "passive"))
      (node (ref "C28") (pin "1") (pinfunction "1_1") (pintype "passive"))
      (node (ref "C29") (pin "1") (pinfunction "1_1") (pintype "passive"))
      (node (ref "C3") (pin "2") (pinfunction "2_2") (pintype "passive"))
      (node (ref "C30") (pin "2") (pinfunction "2_2") (pintype "passive"))
      (node (ref "C31") (pin "2") (pinfunction "2_2") (pintype "passive"))
      (node (ref "C32") (pin "2") (pinfunction "2_2") (pintype "passive"))
      (node (ref "C8") (pin "2") (pinfunction "2_2") (pintype "passive"))
      (node (ref "C9") (pin "2") (pinfunction "2_2") (pintype "passive"))
      (node (ref "COLOR/START") (pin "1") (pinfunction "1_1") (pintype "passive"))
      (node (ref "COLOR/START") (pin "3") (pinfunction "3_3") (pintype "passive"))
      (node (ref "H1") (pin "B3,3") (pinfunction "MOUNT_B3,3") (pintype "passive"))
      (node (ref "H2") (pin "B3,3") (pinfunction "MOUNT_B3,3") (pintype "passive"))
      (node (ref "H3") (pin "B3,3") (pinfunction "MOUNT_B3,3") (pintype "passive"))
      (node (ref "IC1") (pin "15") (pinfunction "GND_15") (pintype "power_in"))
      (node (ref "IC2") (pin "15") (pinfunction "GND_15") (pintype "power_in"))
      (node (ref "IC3") (pin "GND") (pinfunction "GND_GND") (pintype "bidirectional"))
      (node (ref "IC4") (pin "GND") (pinfunction "GND_GND") (pintype "bidirectional"))
      (node (ref "IC6") (pin "14") (pinfunction "GND_14") (pintype "bidirectional"))
      (node (ref "IC6") (pin "24") (pinfunction "GND_24") (pintype "bidirectional"))
      (node (ref "IC6") (pin "34") (pinfunction "GND_34") (pintype "bidirectional"))
      (node (ref "IC6") (pin "44") (pinfunction "GND_44") (pintype "bidirectional"))
      (node (ref "IC6") (pin "52") (pinfunction "GND_52") (pintype "bidirectional"))
      (node (ref "IC6") (pin "60") (pinfunction "GND_60") (pintype "bidirectional"))
      (node (ref "IC7") (pin "7") (pinfunction "GND_7") (pintype "bidirectional"))
      (node (ref "JB2") (pin "1") (pinfunction "1_1") (pintype "passive"))
      (node (ref "JC2") (pin "1") (pinfunction "1_1") (pintype "passive"))
      (node (ref "LA1") (pin "C") (pinfunction "C_C") (pintype "passive"))
      (node (ref "LA2") (pin "C") (pinfunction "C_C") (pintype "passive"))
      (node (ref "LA3") (pin "C") (pinfunction "C_C") (pintype "passive"))
      (node (ref "LA4") (pin "C") (pinfunction "C_C") (pintype "passive"))
      (node (ref "LB3") (pin "C") (pinfunction "C_C") (pintype "passive"))
      (node (ref "LB4") (pin "C") (pinfunction "C_C") (pintype "passive"))
      (node (ref "LB5") (pin "C") (pinfunction "C_C") (pintype "passive"))
      (node (ref "LB6") (pin "C") (pinfunction "C_C") (pintype "passive"))
      (node (ref "PRG") (pin "6") (pinfunction "GND_6") (pintype "passive"))
      (node (ref "R1") (pin "1") (pinfunction "1_1") (pintype "bidirectional"))
      (node (ref "R15") (pin "1") (pinfunction "1_1") (pintype "bidirectional"))
      (node (ref "R16") (pin "1") (pinfunction "1_1") (pintype "bidirectional"))
      (node (ref "R17") (pin "1") (pinfunction "1_1") (pintype "bidirectional"))
      (node (ref "R21") (pin "1") (pinfunction "1_1") (pintype "bidirectional"))
      (node (ref "R22") (pin "1") (pinfunction "1_1") (pintype "bidirectional"))
      (node (ref "R33") (pin "2") (pinfunction "2_2") (pintype "bidirectional"))
      (node (ref "R34") (pin "1") (pinfunction "1_1") (pintype "bidirectional"))
      (node (ref "R35") (pin "1") (pinfunction "1_1") (pintype "bidirectional"))
      (node (ref "R38") (pin "1") (pinfunction "1_1") (pintype "bidirectional"))
      (node (ref "R39") (pin "1") (pinfunction "1_1") (pintype "bidirectional"))
      (node (ref "R40") (pin "1") (pinfunction "1_1") (pintype "bidirectional"))
      (node (ref "R41") (pin "1") (pinfunction "1_1") (pintype "bidirectional"))
      (node (ref "R42") (pin "1") (pinfunction "1_1") (pintype "bidirectional"))
      (node (ref "SD1") (pin "VSS") (pinfunction "VSS_VSS") (pintype "bidirectional"))
      (node (ref "T1") (pin "E") (pinfunction "E_E") (pintype "passive"))
      (node (ref "T2") (pin "E") (pinfunction "E_E") (pintype "passive"))
      (node (ref "T3") (pin "E") (pinfunction "E_E") (pintype "passive"))
      (node (ref "UART_C0") (pin "2") (pinfunction "GND_2") (pintype "passive"))
      (node (ref "UART_D0") (pin "2") (pinfunction "GND_2") (pintype "passive"))
      (node (ref "UART_E0") (pin "2") (pinfunction "GND_2") (pintype "passive"))
      (node (ref "USB") (pin "5") (pinfunction "5_5") (pintype "input"))
      (node (ref "XB1") (pin "10") (pinfunction "GND_10") (pintype "power_in"))
    )
    (net (code "54") (name "GND1") (class "Default")
      (node (ref "C26") (pin "2") (pinfunction "2_2") (pintype "passive"))
      (node (ref "IC5") (pin "2") (pinfunction "GND_2") (pintype "bidirectional"))
      (node (ref "IC5") (pin "3") (pinfunction "DATA_3") (pintype "bidirectional"))
      (node (ref "IC5") (pin "4") (pinfunction "DATA_4") (pintype "bidirectional"))
      (node (ref "R33") (pin "1") (pinfunction "1_1") (pintype "bidirectional"))
      (node (ref "USB") (pin "M1") (pinfunction "S1_M1") (pintype "passive"))
      (node (ref "USB") (pin "M2") (pinfunction "S2_M2") (pintype "passive"))
      (node (ref "USB") (pin "M3") (pinfunction "S3_M3") (pintype "passive"))
      (node (ref "USB") (pin "M4") (pinfunction "S4_M4") (pintype "passive"))
    )
    (net (code "55") (name "Net-(C13-Pad1)") (class "Default")
      (node (ref "C13") (pin "1") (pinfunction "1_1") (pintype "passive"))
      (node (ref "D1") (pin "C") (pinfunction "C_C") (pintype "passive"))
      (node (ref "IC3") (pin "IN") (pinfunction "IN_IN") (pintype "bidirectional"))
      (node (ref "IC4") (pin "IN") (pinfunction "IN_IN") (pintype "bidirectional"))
      (node (ref "R23") (pin "2") (pinfunction "2_2") (pintype "bidirectional"))
    )
    (net (code "56") (name "Net-(C27-Pad1)") (class "Default")
      (node (ref "C27") (pin "1") (pinfunction "1_1") (pintype "passive"))
      (node (ref "C28") (pin "2") (pinfunction "2_2") (pintype "passive"))
      (node (ref "R24") (pin "2") (pinfunction "2_2") (pintype "bidirectional"))
    )
    (net (code "57") (name "Net-(C27-Pad2)") (class "Default")
      (node (ref "C27") (pin "2") (pinfunction "2_2") (pintype "passive"))
      (node (ref "R25") (pin "1") (pinfunction "1_1") (pintype "bidirectional"))
    )
    (net (code "58") (name "Net-(IC1A-C1+)") (class "Default")
      (node (ref "C4") (pin "1") (pinfunction "1_1") (pintype "passive"))
      (node (ref "IC1") (pin "1") (pinfunction "C1+_1") (pintype "bidirectional"))
    )
    (net (code "59") (name "Net-(IC1A-C1-)") (class "Default")
      (node (ref "C4") (pin "2") (pinfunction "2_2") (pintype "passive"))
      (node (ref "IC1") (pin "3") (pinfunction "C1-_3") (pintype "bidirectional"))
    )
    (net (code "60") (name "Net-(IC1A-C2+)") (class "Default")
      (node (ref "C5") (pin "1") (pinfunction "1_1") (pintype "passive"))
      (node (ref "IC1") (pin "4") (pinfunction "C2+_4") (pintype "bidirectional"))
    )
    (net (code "61") (name "Net-(IC1A-C2-)") (class "Default")
      (node (ref "C5") (pin "2") (pinfunction "2_2") (pintype "passive"))
      (node (ref "IC1") (pin "5") (pinfunction "C2-_5") (pintype "bidirectional"))
    )
    (net (code "62") (name "Net-(IC1A-V+)") (class "Default")
      (node (ref "C11") (pin "1") (pinfunction "1_1") (pintype "passive"))
      (node (ref "IC1") (pin "2") (pinfunction "V+_2") (pintype "bidirectional"))
    )
    (net (code "63") (name "Net-(IC2A-C1+)") (class "Default")
      (node (ref "C6") (pin "1") (pinfunction "1_1") (pintype "passive"))
      (node (ref "IC2") (pin "1") (pinfunction "C1+_1") (pintype "bidirectional"))
    )
    (net (code "64") (name "Net-(IC2A-C1-)") (class "Default")
      (node (ref "C6") (pin "2") (pinfunction "2_2") (pintype "passive"))
      (node (ref "IC2") (pin "3") (pinfunction "C1-_3") (pintype "bidirectional"))
    )
    (net (code "65") (name "Net-(IC2A-C2+)") (class "Default")
      (node (ref "C7") (pin "1") (pinfunction "1_1") (pintype "passive"))
      (node (ref "IC2") (pin "4") (pinfunction "C2+_4") (pintype "bidirectional"))
    )
    (net (code "66") (name "Net-(IC2A-C2-)") (class "Default")
      (node (ref "C7") (pin "2") (pinfunction "2_2") (pintype "passive"))
      (node (ref "IC2") (pin "5") (pinfunction "C2-_5") (pintype "bidirectional"))
    )
    (net (code "67") (name "Net-(IC2A-V+)") (class "Default")
      (node (ref "C12") (pin "1") (pinfunction "1_1") (pintype "passive"))
      (node (ref "IC2") (pin "2") (pinfunction "V+_2") (pintype "bidirectional"))
    )
    (net (code "68") (name "Net-(IC2A-V-)") (class "Default")
      (node (ref "C9") (pin "1") (pinfunction "1_1") (pintype "passive"))
      (node (ref "IC2") (pin "6") (pinfunction "V-_6") (pintype "bidirectional"))
    )
    (net (code "69") (name "Net-(IC6-AVCC)") (class "Default")
      (node (ref "C18") (pin "1") (pinfunction "1_1") (pintype "passive"))
      (node (ref "IC6") (pin "61") (pinfunction "AVCC_61") (pintype "bidirectional"))
      (node (ref "L1") (pin "1") (pinfunction "1_1") (pintype "passive"))
    )
    (net (code "70") (name "Net-(IC6-PR0{slash}XTAL2)") (class "Default")
      (node (ref "C25") (pin "1") (pinfunction "1_1") (pintype "passive"))
      (node (ref "IC6") (pin "58") (pinfunction "PR0/XTAL2_58") (pintype "bidirectional"))
      (node (ref "Q1") (pin "2") (pinfunction "2_2") (pintype "passive"))
    )
    (net (code "71") (name "Net-(IC6-PR1{slash}XTAL1)") (class "Default")
      (node (ref "C24") (pin "1") (pinfunction "1_1") (pintype "passive"))
      (node (ref "IC6") (pin "59") (pinfunction "PR1/XTAL1_59") (pintype "bidirectional"))
      (node (ref "Q1") (pin "1") (pinfunction "1_1") (pintype "passive"))
    )
    (net (code "72") (name "Net-(IC7-+IN)") (class "Default")
      (node (ref "C29") (pin "2") (pinfunction "2_2") (pintype "passive"))
      (node (ref "IC7") (pin "2") (pinfunction "BYPASS_2") (pintype "bidirectional"))
      (node (ref "IC7") (pin "3") (pinfunction "+IN_3") (pintype "bidirectional"))
    )
    (net (code "73") (name "Net-(IC7--IN)") (class "Default")
      (node (ref "IC7") (pin "4") (pinfunction "-IN_4") (pintype "bidirectional"))
      (node (ref "R25") (pin "2") (pinfunction "2_2") (pintype "bidirectional"))
      (node (ref "R37") (pin "1") (pinfunction "1_1") (pintype "bidirectional"))
    )
    (net (code "74") (name "Net-(IC7-VO1)") (class "Default")
      (node (ref "HP") (pin "3") (pinfunction "3_3") (pintype "passive"))
      (node (ref "HP") (pin "4") (pinfunction "4_4") (pintype "passive"))
      (node (ref "IC7") (pin "5") (pinfunction "VO1_5") (pintype "bidirectional"))
      (node (ref "R37") (pin "2") (pinfunction "2_2") (pintype "bidirectional"))
    )
    (net (code "75") (name "Net-(IC7-VO2)") (class "Default")
      (node (ref "HP") (pin "5") (pinfunction "5_5") (pintype "passive"))
      (node (ref "IC7") (pin "8") (pinfunction "VO2_8") (pintype "bidirectional"))
    )
    (net (code "76") (name "Net-(LA1-PadA)") (class "Default")
      (node (ref "LA1") (pin "A") (pinfunction "A_A") (pintype "passive"))
      (node (ref "R5") (pin "1") (pinfunction "1_1") (pintype "bidirectional"))
    )
    (net (code "77") (name "Net-(LA2-PadA)") (class "Default")
      (node (ref "LA2") (pin "A") (pinfunction "A_A") (pintype "passive"))
      (node (ref "R4") (pin "1") (pinfunction "1_1") (pintype "bidirectional"))
    )
    (net (code "78") (name "Net-(LA3-PadA)") (class "Default")
      (node (ref "LA3") (pin "A") (pinfunction "A_A") (pintype "passive"))
      (node (ref "R7") (pin "1") (pinfunction "1_1") (pintype "bidirectional"))
    )
    (net (code "79") (name "Net-(LA4-PadA)") (class "Default")
      (node (ref "LA4") (pin "A") (pinfunction "A_A") (pintype "passive"))
      (node (ref "R6") (pin "1") (pinfunction "1_1") (pintype "bidirectional"))
    )
    (net (code "80") (name "Net-(LB3-PadA)") (class "Default")
      (node (ref "LB3") (pin "A") (pinfunction "A_A") (pintype "passive"))
      (node (ref "R8") (pin "1") (pinfunction "1_1") (pintype "bidirectional"))
    )
    (net (code "81") (name "Net-(LB4-PadA)") (class "Default")
      (node (ref "LB4") (pin "A") (pinfunction "A_A") (pintype "passive"))
      (node (ref "R9") (pin "1") (pinfunction "1_1") (pintype "bidirectional"))
    )
    (net (code "82") (name "Net-(LB5-PadA)") (class "Default")
      (node (ref "LB5") (pin "A") (pinfunction "A_A") (pintype "passive"))
      (node (ref "R10") (pin "1") (pinfunction "1_1") (pintype "bidirectional"))
    )
    (net (code "83") (name "Net-(LB6-PadA)") (class "Default")
      (node (ref "LB6") (pin "A") (pinfunction "A_A") (pintype "passive"))
      (node (ref "R11") (pin "1") (pinfunction "1_1") (pintype "bidirectional"))
    )
    (net (code "84") (name "Net-(LED1A-A)") (class "Default")
      (node (ref "LED1") (pin "6") (pinfunction "A_6") (pintype "passive"))
      (node (ref "R18") (pin "1") (pinfunction "1_1") (pintype "bidirectional"))
    )
    (net (code "85") (name "Net-(LED1A-C)") (class "Default")
      (node (ref "LED1") (pin "1") (pinfunction "C_1") (pintype "passive"))
      (node (ref "T1") (pin "C") (pinfunction "C_C") (pintype "passive"))
    )
    (net (code "86") (name "Net-(LED1B-A)") (class "Default")
      (node (ref "LED1") (pin "5") (pinfunction "A_5") (pintype "passive"))
      (node (ref "R19") (pin "1") (pinfunction "1_1") (pintype "bidirectional"))
    )
    (net (code "87") (name "Net-(LED1B-C)") (class "Default")
      (node (ref "LED1") (pin "2") (pinfunction "C_2") (pintype "passive"))
      (node (ref "T2") (pin "C") (pinfunction "C_C") (pintype "passive"))
    )
    (net (code "88") (name "Net-(LED1C-A)") (class "Default")
      (node (ref "LED1") (pin "4") (pinfunction "A_4") (pintype "passive"))
      (node (ref "R20") (pin "1") (pinfunction "1_1") (pintype "bidirectional"))
    )
    (net (code "89") (name "Net-(LED1C-C)") (class "Default")
      (node (ref "LED1") (pin "3") (pinfunction "C_3") (pintype "passive"))
      (node (ref "T3") (pin "C") (pinfunction "C_C") (pintype "passive"))
    )
    (net (code "90") (name "Net-(LW_BAT-PadC)") (class "Default")
      (node (ref "LW_BAT") (pin "C") (pinfunction "C_C") (pintype "passive"))
      (node (ref "R21") (pin "2") (pinfunction "2_2") (pintype "bidirectional"))
    )
    (net (code "91") (name "Net-(R12-Pad2)") (class "Default")
      (node (ref "R12") (pin "2") (pinfunction "2_2") (pintype "bidirectional"))
      (node (ref "T1") (pin "B") (pinfunction "B_B") (pintype "passive"))
    )
    (net (code "92") (name "Net-(R13-Pad2)") (class "Default")
      (node (ref "R13") (pin "2") (pinfunction "2_2") (pintype "bidirectional"))
      (node (ref "T2") (pin "B") (pinfunction "B_B") (pintype "passive"))
    )
    (net (code "93") (name "Net-(R14-Pad2)") (class "Default")
      (node (ref "R14") (pin "2") (pinfunction "2_2") (pintype "bidirectional"))
      (node (ref "T3") (pin "B") (pinfunction "B_B") (pintype "passive"))
    )
    (net (code "94") (name "unconnected-(IC1A-R2OUT-Pad9)") (class "Default")
      (node (ref "IC1") (pin "9") (pinfunction "R2OUT_9") (pintype "output"))
    )
    (net (code "95") (name "unconnected-(IC1A-T1OUT-Pad14)") (class "Default")
      (node (ref "IC1") (pin "14") (pinfunction "T1OUT_14") (pintype "output"))
    )
    (net (code "96") (name "unconnected-(IC6-PA5{slash}ADCA5-Pad3)") (class "Default")
      (node (ref "IC6") (pin "3") (pinfunction "PA5/ADCA5_3") (pintype "bidirectional"))
    )
    (net (code "97") (name "unconnected-(IC6-PA6{slash}ADCA6-Pad4)") (class "Default")
      (node (ref "IC6") (pin "4") (pinfunction "PA6/ADCA6_4") (pintype "bidirectional"))
    )
    (net (code "98") (name "unconnected-(IC6-PB0{slash}ADCB0{slash}AREF-Pad6)") (class "Default")
      (node (ref "IC6") (pin "6") (pinfunction "PB0/ADCB0/AREF_6") (pintype "bidirectional"))
    )
    (net (code "99") (name "unconnected-(IC6-PB1{slash}ADCB1-Pad7)") (class "Default")
      (node (ref "IC6") (pin "7") (pinfunction "PB1/ADCB1_7") (pintype "bidirectional"))
    )
    (net (code "100") (name "unconnected-(IC6-PC4{slash}OC1A{slash}\\S\\S-Pad20)") (class "Default")
      (node (ref "IC6") (pin "20") (pinfunction "PC4/OC1A/\\S\\S_20") (pintype "bidirectional"))
    )
    (net (code "101") (name "unconnected-(IC6-PD5{slash}OC1B{slash}XCK1{slash}MOSI-Pad31)") (class "Default")
      (node (ref "IC6") (pin "31") (pinfunction "PD5/OC1B/XCK1/MOSI_31") (pintype "bidirectional"))
    )
    (net (code "102") (name "unconnected-(IC6-SCL{slash}XCK0{slash}OC0B{slash}PE1-Pad37)") (class "Default")
      (node (ref "IC6") (pin "37") (pinfunction "SCL/XCK0/OC0B/PE1_37") (pintype "bidirectional"))
    )
    (net (code "103") (name "unconnected-(IC6-SDA{slash}OC0A{slash}PE0-Pad36)") (class "Default")
      (node (ref "IC6") (pin "36") (pinfunction "SDA/OC0A/PE0_36") (pintype "bidirectional"))
    )
    (net (code "104") (name "unconnected-(JB2-Pad2)") (class "Default")
      (node (ref "JB2") (pin "2") (pinfunction "2_2") (pintype "passive"))
    )
    (net (code "105") (name "unconnected-(JB2-Pad3)") (class "Default")
      (node (ref "JB2") (pin "3") (pinfunction "3_3") (pintype "passive"))
    )
    (net (code "106") (name "unconnected-(JB2-Pad4)") (class "Default")
      (node (ref "JB2") (pin "4") (pinfunction "4_4") (pintype "passive"))
    )
    (net (code "107") (name "unconnected-(JB2-Pad5)") (class "Default")
      (node (ref "JB2") (pin "5") (pinfunction "5_5") (pintype "passive"))
    )
    (net (code "108") (name "unconnected-(JB2-Pad6)") (class "Default")
      (node (ref "JB2") (pin "6") (pinfunction "6_6") (pintype "passive"))
    )
    (net (code "109") (name "unconnected-(JB2-Pad7)") (class "Default")
      (node (ref "JB2") (pin "7") (pinfunction "7_7") (pintype "passive"))
    )
    (net (code "110") (name "unconnected-(JB2-Pad8)") (class "Default")
      (node (ref "JB2") (pin "8") (pinfunction "8_8") (pintype "passive"))
    )
    (net (code "111") (name "unconnected-(JB2-Pad9)") (class "Default")
      (node (ref "JB2") (pin "9") (pinfunction "9_9") (pintype "passive"))
    )
    (net (code "112") (name "unconnected-(JB2-Pad10)") (class "Default")
      (node (ref "JB2") (pin "10") (pinfunction "10_10") (pintype "passive"))
    )
    (net (code "113") (name "unconnected-(JB2-Pad15)") (class "Default")
      (node (ref "JB2") (pin "15") (pinfunction "15_15") (pintype "passive"))
    )
    (net (code "114") (name "unconnected-(JB2-Pad16)") (class "Default")
      (node (ref "JB2") (pin "16") (pinfunction "16_16") (pintype "passive"))
    )
    (net (code "115") (name "unconnected-(JC2-Pad3)") (class "Default")
      (node (ref "JC2") (pin "3") (pinfunction "3_3") (pintype "passive"))
    )
    (net (code "116") (name "unconnected-(JC2-Pad5)") (class "Default")
      (node (ref "JC2") (pin "5") (pinfunction "5_5") (pintype "passive"))
    )
    (net (code "117") (name "unconnected-(JC2-Pad7)") (class "Default")
      (node (ref "JC2") (pin "7") (pinfunction "7_7") (pintype "passive"))
    )
    (net (code "118") (name "unconnected-(JC2-Pad8)") (class "Default")
      (node (ref "JC2") (pin "8") (pinfunction "8_8") (pintype "passive"))
    )
    (net (code "119") (name "unconnected-(JC2-Pad9)") (class "Default")
      (node (ref "JC2") (pin "9") (pinfunction "9_9") (pintype "passive"))
    )
    (net (code "120") (name "unconnected-(JC2-Pad10)") (class "Default")
      (node (ref "JC2") (pin "10") (pinfunction "10_10") (pintype "passive"))
    )
    (net (code "121") (name "unconnected-(JC2-Pad11)") (class "Default")
      (node (ref "JC2") (pin "11") (pinfunction "11_11") (pintype "passive"))
    )
    (net (code "122") (name "unconnected-(JC2-Pad12)") (class "Default")
      (node (ref "JC2") (pin "12") (pinfunction "12_12") (pintype "passive"))
    )
    (net (code "123") (name "unconnected-(JC2-Pad13)") (class "Default")
      (node (ref "JC2") (pin "13") (pinfunction "13_13") (pintype "passive"))
    )
    (net (code "124") (name "unconnected-(JC2-Pad14)") (class "Default")
      (node (ref "JC2") (pin "14") (pinfunction "14_14") (pintype "passive"))
    )
    (net (code "125") (name "unconnected-(JC2-Pad15)") (class "Default")
      (node (ref "JC2") (pin "15") (pinfunction "15_15") (pintype "passive"))
    )
    (net (code "126") (name "unconnected-(JC2-Pad16)") (class "Default")
      (node (ref "JC2") (pin "16") (pinfunction "16_16") (pintype "passive"))
    )
    (net (code "127") (name "unconnected-(PRG-NC-Pad3)") (class "Default")
      (node (ref "PRG") (pin "3") (pinfunction "NC_3") (pintype "passive"))
    )
    (net (code "128") (name "unconnected-(PRG-NC.-Pad4)") (class "Default")
      (node (ref "PRG") (pin "4") (pinfunction "NC._4") (pintype "passive"))
    )
    (net (code "129") (name "unconnected-(SD1-PadDAT1)") (class "Default")
      (node (ref "SD1") (pin "DAT1") (pinfunction "DAT1_DAT1") (pintype "bidirectional"))
    )
    (net (code "130") (name "unconnected-(SD1-PadDAT2)") (class "Default")
      (node (ref "SD1") (pin "DAT2") (pinfunction "DAT2_DAT2") (pintype "bidirectional"))
    )
    (net (code "131") (name "unconnected-(USB-Pad4)") (class "Default")
      (node (ref "USB") (pin "4") (pinfunction "4_4") (pintype "input"))
    )
    (net (code "132") (name "unconnected-(XB1-AD0{slash}DIO0-Pad20)") (class "Default")
      (node (ref "XB1") (pin "20") (pinfunction "AD0/DIO0_20") (pintype "bidirectional"))
    )
    (net (code "133") (name "unconnected-(XB1-AD1{slash}DIO1-Pad19)") (class "Default")
      (node (ref "XB1") (pin "19") (pinfunction "AD1/DIO1_19") (pintype "bidirectional"))
    )
    (net (code "134") (name "unconnected-(XB1-AD2{slash}DIO2-Pad18)") (class "Default")
      (node (ref "XB1") (pin "18") (pinfunction "AD2/DIO2_18") (pintype "bidirectional"))
    )
    (net (code "135") (name "unconnected-(XB1-ASSOC{slash}AD5{slash}DIO5-Pad15)") (class "Default")
      (node (ref "XB1") (pin "15") (pinfunction "ASSOC/AD5/DIO5_15") (pintype "bidirectional"))
    )
    (net (code "136") (name "unconnected-(XB1-CD{slash}DOUT_EN{slash}DO8-Pad4)") (class "Default")
      (node (ref "XB1") (pin "4") (pinfunction "CD/DOUT_EN/DO8_4") (pintype "output"))
    )
    (net (code "137") (name "unconnected-(XB1-COORD_SEL{slash}AD3{slash}DIO3-Pad17)") (class "Default")
      (node (ref "XB1") (pin "17") (pinfunction "COORD_SEL/AD3/DIO3_17") (pintype "bidirectional"))
    )
    (net (code "138") (name "unconnected-(XB1-ON{slash}~{SLEEP}-Pad13)") (class "Default")
      (node (ref "XB1") (pin "13") (pinfunction "ON/~{SLEEP}_13") (pintype "output"))
    )
    (net (code "139") (name "unconnected-(XB1-PWM0{slash}RSSI-Pad6)") (class "Default")
      (node (ref "XB1") (pin "6") (pinfunction "PWM0/RSSI_6") (pintype "output"))
    )
    (net (code "140") (name "unconnected-(XB1-RF_TX{slash}AD4{slash}DIO4-Pad11)") (class "Default")
      (node (ref "XB1") (pin "11") (pinfunction "RF_TX/AD4/DIO4_11") (pintype "bidirectional"))
    )
    (net (code "141") (name "unconnected-(XB1-VREF-Pad14)") (class "Default")
      (node (ref "XB1") (pin "14") (pinfunction "VREF_14") (pintype "input"))
    )
    (net (code "142") (name "unconnected-(XB1-~{DTR}{slash}SLEEP_RQ{slash}DI8-Pad9)") (class "Default")
      (node (ref "XB1") (pin "9") (pinfunction "~{DTR}/SLEEP_RQ/DI8_9") (pintype "bidirectional"))
    )
    (net (code "143") (name "unconnected-(XB1-~{RESET}-Pad5)") (class "Default")
      (node (ref "XB1") (pin "5") (pinfunction "~{RESET}_5") (pintype "input"))
    )
  )
)
